# UsbToUart.net
KiCad netlist of a schematic drawn in Altium Designer
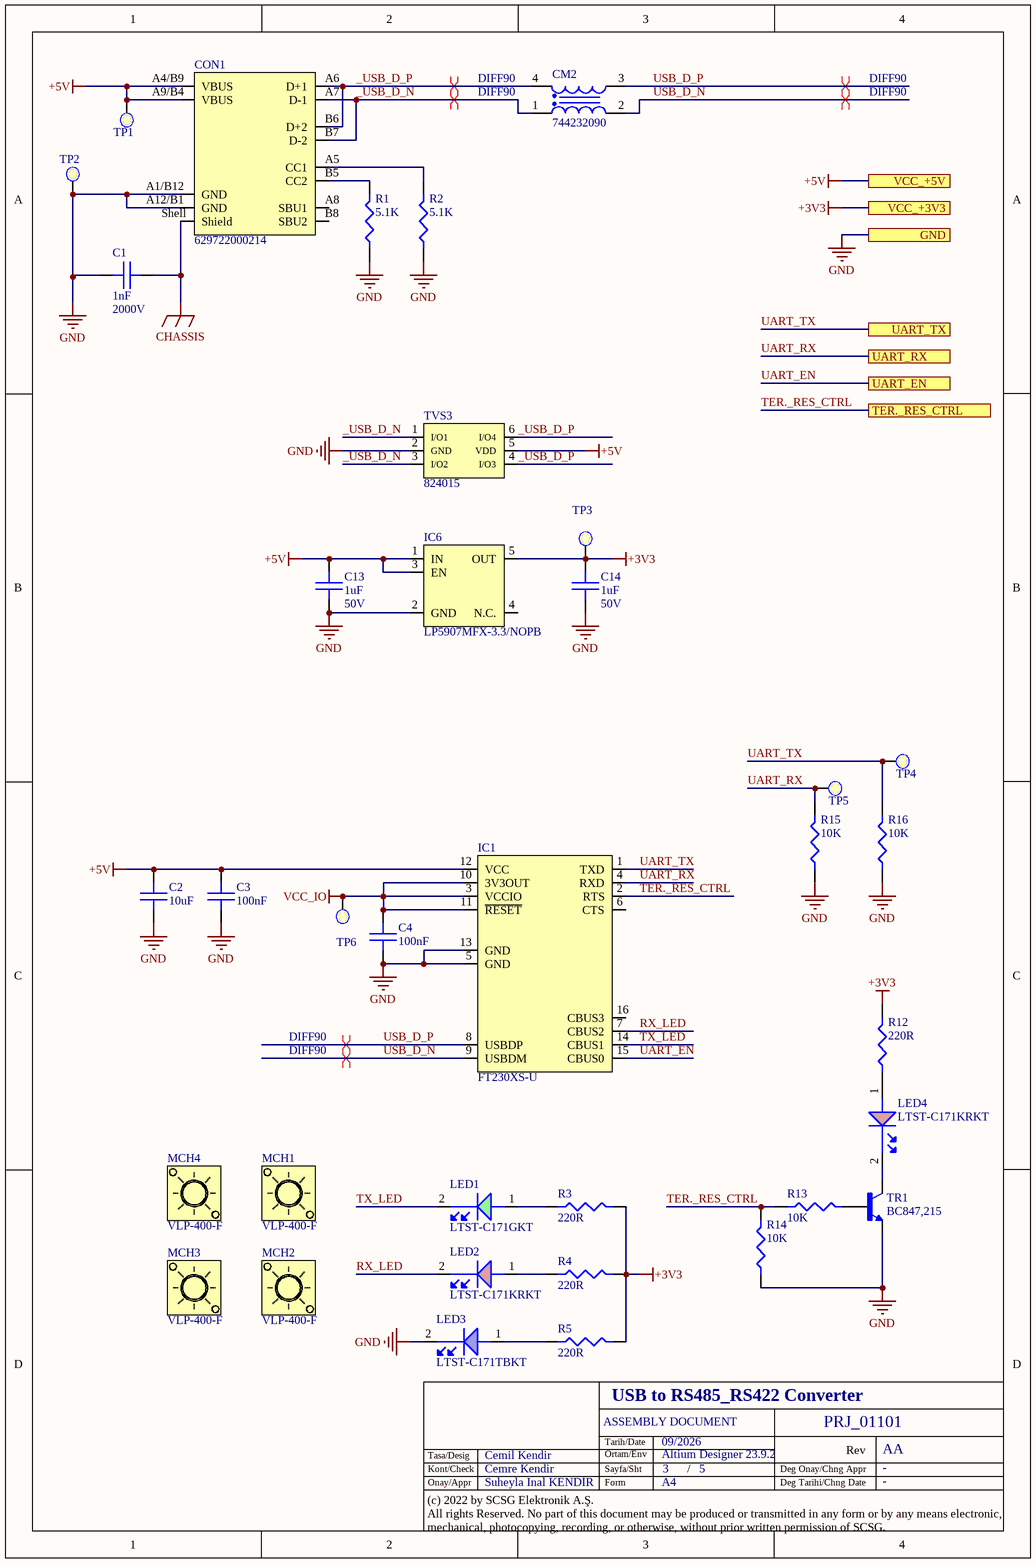
[diagram p0: UsbToUart.SchDoc]

(export (version "E")
  (design (tool "Eeschema 10.0.6"))
  (components
    (comp (ref "C1")
      (value "1nF")
      (footprint "C1206")
      (description "1nF, 2kV, X7R, 1206")
      (fields
        (field (name "MANUFACTURER") "Yageo")
        (field (name "MANUFACTURER PART NUMBER") "CS1206KKX7RDBB102")
        (field (name "VOLTAGE RATING") "2000V")
      )
      (libsource (lib "Capacitor") (part "CS1206KKX7RDBB102"))
    )
    (comp (ref "C2")
      (value "10uF")
      (footprint "C0805")
      (description "10uF ,10V ,X7R ,0805")
      (fields
        (field (name "MANUFACTURER") "Yageo")
        (field (name "MANUFACTURER PART NUMBER") "CC0805KFX7R6BB106")
      )
      (libsource (lib "Capacitor") (part "CC0805KFX7R6BB106"))
    )
    (comp (ref "C3")
      (value "100nF")
      (footprint "C0603")
      (description "100nF, 25V, X7R, 0603")
      (fields
        (field (name "MANUFACTURER") "Yageo")
        (field (name "MANUFACTURER PART NUMBER") "CC0603KRX7R8BB104")
      )
      (libsource (lib "Capacitor") (part "CC0603KRX7R8BB104"))
    )
    (comp (ref "C4")
      (value "100nF")
      (footprint "C0603")
      (description "100nF, 25V, X7R, 0603")
      (fields
        (field (name "MANUFACTURER") "Yageo")
        (field (name "MANUFACTURER PART NUMBER") "CC0603KRX7R8BB104")
      )
      (libsource (lib "Capacitor") (part "CC0603KRX7R8BB104"))
    )
    (comp (ref "C13")
      (value "1uF")
      (footprint "C0603")
      (description "1uF, 50V, X7R, 0603")
      (fields
        (field (name "MANUFACTURER") "Yageo")
        (field (name "MANUFACTURER PART NUMBER") "CC0603KRX7R9BB105")
        (field (name "VOLTAGE RATING") "50V")
      )
      (libsource (lib "Capacitor") (part "CC0603KRX7R9BB105"))
    )
    (comp (ref "C14")
      (value "1uF")
      (footprint "C0603")
      (description "1uF, 50V, X7R, 0603")
      (fields
        (field (name "MANUFACTURER") "Yageo")
        (field (name "MANUFACTURER PART NUMBER") "CC0603KRX7R9BB105")
        (field (name "VOLTAGE RATING") "50V")
      )
      (libsource (lib "Capacitor") (part "CC0603KRX7R9BB105"))
    )
    (comp (ref "CM2")
      (value "744232090")
      (footprint "WE-CNSW_1206")
      (description "Common Mode Chokes Dual 90Ohm 100MHz 370mA SMD T/R")
      (fields (field (name "MANUFACTURER") "Wurth Electronics"))
      (libsource (lib "Inductor") (part "744232090"))
    )
    (comp (ref "CON1")
      (value "629722000214")
      (footprint "629722000214")
      (description "Wr-com_usb 2.0_TYPE C_horizontal")
      (fields (field (name "MANUFACTURER") "Wurth Elektronik"))
      (libsource (lib "Connectors") (part "629722000214"))
    )
    (comp (ref "IC1")
      (value "FT230XS-U")
      (footprint "SSOP-16")
      (description "USB Interface IC USB to Basic Serial UART IC SSOP-16")
      (fields (field (name "MANUFACTURER") "FTDI"))
      (libsource (lib "IntegratedCircuit") (part "FT230XS-U"))
    )
    (comp (ref "IC6")
      (value "LP5907MFX-3.3/NOPB")
      (footprint "SOT23-5")
      (description "Linear Voltage Regulator IC Positive Fixed 1 Output 250mA SOT-23-5")
      (fields (field (name "MANUFACTURER") "TEXAS"))
      (libsource (lib "IntegratedCircuit") (part "LP5907MFX-3.3/NOPB"))
    )
    (comp (ref "LED1")
      (value "LTST-C171GKT")
      (footprint "0805_green")
      (description "LED GREEN CLEAR CHIP SMD")
      (fields (field (name "MANUFACTURER") "Vishay Lite-On"))
      (libsource (lib "Diode") (part "LTST-C171GKT"))
    )
    (comp (ref "LED2")
      (value "LTST-C171KRKT")
      (footprint "0805_RED")
      (description "LED RED CLEAR SMD")
      (fields (field (name "MANUFACTURER") "Vishay Lite-On"))
      (libsource (lib "Diode") (part "LTST-C171KRKT"))
    )
    (comp (ref "LED3")
      (value "LTST-C171TBKT")
      (footprint "0805_blue")
      (description "LED BLUE CLEAR CHIP SMD")
      (fields (field (name "MANUFACTURER") "Vishay Lite-On"))
      (libsource (lib "Diode") (part "LTST-C171TBKT"))
    )
    (comp (ref "LED4")
      (value "LTST-C171KRKT")
      (footprint "0805_RED")
      (description "LED RED CLEAR SMD")
      (fields (field (name "MANUFACTURER") "Vishay Lite-On"))
      (libsource (lib "Diode") (part "LTST-C171KRKT"))
    )
    (comp (ref "MCH1")
      (value "VLP-400-F")
      (footprint "VLP-400-F")
      (description "Bivar straight light guide, rigidity, PCBinstall, 4.1 x 4.1 x 10.2mm")
      (fields (field (name "MANUFACTURER") "Bivar"))
      (libsource (lib "Mechanical") (part "VLP-400-F"))
    )
    (comp (ref "MCH2")
      (value "VLP-400-F")
      (footprint "VLP-400-F")
      (description "Bivar straight light guide, rigidity, PCBinstall, 4.1 x 4.1 x 10.2mm")
      (fields (field (name "MANUFACTURER") "Bivar"))
      (libsource (lib "Mechanical") (part "VLP-400-F"))
    )
    (comp (ref "MCH3")
      (value "VLP-400-F")
      (footprint "VLP-400-F")
      (description "Bivar straight light guide, rigidity, PCBinstall, 4.1 x 4.1 x 10.2mm")
      (fields (field (name "MANUFACTURER") "Bivar"))
      (libsource (lib "Mechanical") (part "VLP-400-F"))
    )
    (comp (ref "MCH4")
      (value "VLP-400-F")
      (footprint "VLP-400-F")
      (description "Bivar straight light guide, rigidity, PCBinstall, 4.1 x 4.1 x 10.2mm")
      (fields (field (name "MANUFACTURER") "Bivar"))
      (libsource (lib "Mechanical") (part "VLP-400-F"))
    )
    (comp (ref "R1")
      (value "5.1K")
      (footprint "R0402")
      (description "5.1K, %1, 1/16W, 0402")
      (fields
        (field (name "MANUFACTURER") "YAGEO")
        (field (name "MANUFACTURER PART NUMBER") "RC0402FR-075K1L")
      )
      (libsource (lib "Resistor") (part "RC0402FR-075K1L"))
    )
    (comp (ref "R2")
      (value "5.1K")
      (footprint "R0402")
      (description "5.1K, %1, 1/16W, 0402")
      (fields
        (field (name "MANUFACTURER") "YAGEO")
        (field (name "MANUFACTURER PART NUMBER") "RC0402FR-075K1L")
      )
      (libsource (lib "Resistor") (part "RC0402FR-075K1L"))
    )
    (comp (ref "R3")
      (value "220R")
      (footprint "R0603")
      (description "220R, %1, 1/10W, 0603")
      (fields
        (field (name "MANUFACTURER") "YAGEO")
        (field (name "MANUFACTURER PART NUMBER") "RC0603FR-07220RL")
      )
      (libsource (lib "Resistor") (part "RC0603FR-07220RL"))
    )
    (comp (ref "R4")
      (value "220R")
      (footprint "R0603")
      (description "220R, %1, 1/10W, 0603")
      (fields
        (field (name "MANUFACTURER") "YAGEO")
        (field (name "MANUFACTURER PART NUMBER") "RC0603FR-07220RL")
      )
      (libsource (lib "Resistor") (part "RC0603FR-07220RL"))
    )
    (comp (ref "R5")
      (value "220R")
      (footprint "R0603")
      (description "220R, %1, 1/10W, 0603")
      (fields
        (field (name "MANUFACTURER") "YAGEO")
        (field (name "MANUFACTURER PART NUMBER") "RC0603FR-07220RL")
      )
      (libsource (lib "Resistor") (part "RC0603FR-07220RL"))
    )
    (comp (ref "R12")
      (value "220R")
      (footprint "R0603")
      (description "220R, %1, 1/10W, 0603")
      (fields
        (field (name "MANUFACTURER") "YAGEO")
        (field (name "MANUFACTURER PART NUMBER") "RC0603FR-07220RL")
      )
      (libsource (lib "Resistor") (part "RC0603FR-07220RL"))
    )
    (comp (ref "R13")
      (value "10K")
      (footprint "R0603")
      (description "10K, %1, 1/10W, 0603")
      (fields
        (field (name "MANUFACTURER") "YAGEO")
        (field (name "MANUFACTURER PART NUMBER") "RT0603FRE0710KL")
      )
      (libsource (lib "Resistor") (part "RT0603FRE0710KL"))
    )
    (comp (ref "R14")
      (value "10K")
      (footprint "R0603")
      (description "10K, %1, 1/10W, 0603")
      (fields
        (field (name "MANUFACTURER") "YAGEO")
        (field (name "MANUFACTURER PART NUMBER") "RT0603FRE0710KL")
      )
      (libsource (lib "Resistor") (part "RT0603FRE0710KL"))
    )
    (comp (ref "R15")
      (value "10K")
      (footprint "R0603")
      (description "10K, %1, 1/10W, 0603")
      (fields
        (field (name "MANUFACTURER") "YAGEO")
        (field (name "MANUFACTURER PART NUMBER") "RT0603FRE0710KL")
      )
      (libsource (lib "Resistor") (part "RT0603FRE0710KL"))
    )
    (comp (ref "R16")
      (value "10K")
      (footprint "R0603")
      (description "10K, %1, 1/10W, 0603")
      (fields
        (field (name "MANUFACTURER") "YAGEO")
        (field (name "MANUFACTURER PART NUMBER") "RT0603FRE0710KL")
      )
      (libsource (lib "Resistor") (part "RT0603FRE0710KL"))
    )
    (comp (ref "TP1")
      (value "TestPoint1")
      (footprint "SMD_1mmPoint")
      (description "test ölçüm noktası")
      (fields (field (name "MANUFACTURER") "NO BOM DEVICE"))
      (libsource (lib "Connectors") (part "TestPoint1"))
    )
    (comp (ref "TP2")
      (value "TestPoint1")
      (footprint "SMD_1mmPoint")
      (description "test ölçüm noktası")
      (fields (field (name "MANUFACTURER") "NO BOM DEVICE"))
      (libsource (lib "Connectors") (part "TestPoint1"))
    )
    (comp (ref "TP3")
      (value "TestPoint1")
      (footprint "SMD_1mmPoint")
      (description "test ölçüm noktası")
      (fields (field (name "MANUFACTURER") "NO BOM DEVICE"))
      (libsource (lib "Connectors") (part "TestPoint1"))
    )
    (comp (ref "TP4")
      (value "TestPoint1")
      (footprint "SMD_1mmPoint")
      (description "test ölçüm noktası")
      (fields (field (name "MANUFACTURER") "NO BOM DEVICE"))
      (libsource (lib "Connectors") (part "TestPoint1"))
    )
    (comp (ref "TP5")
      (value "TestPoint1")
      (footprint "SMD_1mmPoint")
      (description "test ölçüm noktası")
      (fields (field (name "MANUFACTURER") "NO BOM DEVICE"))
      (libsource (lib "Connectors") (part "TestPoint1"))
    )
    (comp (ref "TP6")
      (value "TestPoint1")
      (footprint "SMD_1mmPoint")
      (description "test ölçüm noktası")
      (fields (field (name "MANUFACTURER") "NO BOM DEVICE"))
      (libsource (lib "Connectors") (part "TestPoint1"))
    )
    (comp (ref "TR1")
      (value "BC847,215")
      (footprint "SOT23-3")
      (description "TRANS NPN 45V 0.1A SOT23")
      (fields (field (name "MANUFACTURER") "Nexperia"))
      (libsource (lib "Transistor") (part "BC847,215"))
    )
    (comp (ref "TVS3")
      (value "824015")
      (footprint "SOT-23-6")
      (description "WURTH ELEKTRONIK - 824015 - TVS Diode, 82401 Series, Bidirectional, 5 V, 13 V, SOT-23, 6 Pins")
      (fields (field (name "MANUFACTURER") "Wurth Electronics"))
      (libsource (lib "Diode") (part "824015"))
    )
  )
  (nets
    (net (code "1") (name "+3V3") (class "Default")
      (node (ref "C14") (pin "2") (pintype "passive"))
      (node (ref "IC6") (pin "5") (pinfunction "OUT_5") (pintype "passive"))
      (node (ref "R12") (pin "2") (pinfunction "2_2") (pintype "passive"))
      (node (ref "R3") (pin "2") (pinfunction "2_2") (pintype "passive"))
      (node (ref "R4") (pin "2") (pinfunction "2_2") (pintype "passive"))
      (node (ref "R5") (pin "2") (pinfunction "2_2") (pintype "passive"))
      (node (ref "TP3") (pin "1") (pinfunction "1_1") (pintype "passive"))
    )
    (net (code "2") (name "+5V") (class "Default")
      (node (ref "C13") (pin "2") (pintype "passive"))
      (node (ref "C2") (pin "2") (pintype "passive"))
      (node (ref "C3") (pin "2") (pintype "passive"))
      (node (ref "CON1") (pin "A4/B9") (pinfunction "VBUS_A4/B9") (pintype "passive"))
      (node (ref "CON1") (pin "A9/B4") (pinfunction "VBUS_A9/B4") (pintype "passive"))
      (node (ref "IC1") (pin "12") (pinfunction "VCC_12") (pintype "passive"))
      (node (ref "IC6") (pin "1") (pinfunction "IN_1") (pintype "passive"))
      (node (ref "IC6") (pin "3") (pinfunction "EN_3") (pintype "passive"))
      (node (ref "TP1") (pin "1") (pinfunction "1_1") (pintype "passive"))
      (node (ref "TVS3") (pin "5") (pinfunction "VDD_5") (pintype "passive"))
    )
    (net (code "3") (name "/RX_LED") (class "Default")
      (node (ref "IC1") (pin "7") (pinfunction "CBUS2_7") (pintype "passive"))
      (node (ref "LED2") (pin "2") (pinfunction "2_2") (pintype "passive"))
    )
    (net (code "4") (name "/TER._RES_CTRL") (class "Default")
      (node (ref "IC1") (pin "2") (pinfunction "RTS_2") (pintype "passive"))
      (node (ref "R13") (pin "1") (pinfunction "1_1") (pintype "passive"))
      (node (ref "R14") (pin "2") (pinfunction "2_2") (pintype "passive"))
    )
    (net (code "5") (name "/TX_LED") (class "Default")
      (node (ref "IC1") (pin "14") (pinfunction "CBUS1_14") (pintype "passive"))
      (node (ref "LED1") (pin "2") (pinfunction "2_2") (pintype "passive"))
    )
    (net (code "6") (name "/UART_EN") (class "Default")
      (node (ref "IC1") (pin "15") (pinfunction "CBUS0_15") (pintype "passive"))
    )
    (net (code "7") (name "/UART_RX") (class "Default")
      (node (ref "IC1") (pin "4") (pinfunction "RXD_4") (pintype "passive"))
      (node (ref "R15") (pin "2") (pinfunction "2_2") (pintype "passive"))
      (node (ref "TP5") (pin "1") (pinfunction "1_1") (pintype "passive"))
    )
    (net (code "8") (name "/UART_TX") (class "Default")
      (node (ref "IC1") (pin "1") (pinfunction "TXD_1") (pintype "passive"))
      (node (ref "R16") (pin "2") (pinfunction "2_2") (pintype "passive"))
      (node (ref "TP4") (pin "1") (pinfunction "1_1") (pintype "passive"))
    )
    (net (code "9") (name "/USB_D_N") (class "Default")
      (node (ref "CM2") (pin "2") (pinfunction "2_2") (pintype "passive"))
      (node (ref "IC1") (pin "9") (pinfunction "USBDM_9") (pintype "passive"))
    )
    (net (code "10") (name "/USB_D_P") (class "Default")
      (node (ref "CM2") (pin "3") (pinfunction "3_3") (pintype "passive"))
      (node (ref "IC1") (pin "8") (pinfunction "USBDP_8") (pintype "passive"))
    )
    (net (code "11") (name "/_USB_D_N") (class "Default")
      (node (ref "CM2") (pin "1") (pinfunction "1_1") (pintype "passive"))
      (node (ref "CON1") (pin "A7") (pinfunction "D-1_A7") (pintype "passive"))
      (node (ref "CON1") (pin "B7") (pinfunction "D-2_B7") (pintype "passive"))
      (node (ref "TVS3") (pin "1") (pinfunction "I/O1_1") (pintype "passive"))
      (node (ref "TVS3") (pin "3") (pinfunction "I/O2_3") (pintype "passive"))
    )
    (net (code "12") (name "/_USB_D_P") (class "Default")
      (node (ref "CM2") (pin "4") (pinfunction "4_4") (pintype "passive"))
      (node (ref "CON1") (pin "A6") (pinfunction "D+1_A6") (pintype "passive"))
      (node (ref "CON1") (pin "B6") (pinfunction "D+2_B6") (pintype "passive"))
      (node (ref "TVS3") (pin "4") (pinfunction "I/O3_4") (pintype "passive"))
      (node (ref "TVS3") (pin "6") (pinfunction "I/O4_6") (pintype "passive"))
    )
    (net (code "13") (name "CHASSIS") (class "Default")
      (node (ref "C1") (pin "2") (pintype "passive"))
      (node (ref "CON1") (pin "Shell") (pinfunction "Shield_Shell") (pintype "passive"))
    )
    (net (code "14") (name "GND") (class "Default")
      (node (ref "C1") (pin "1") (pintype "passive"))
      (node (ref "C13") (pin "1") (pintype "passive"))
      (node (ref "C14") (pin "1") (pintype "passive"))
      (node (ref "C2") (pin "1") (pintype "passive"))
      (node (ref "C3") (pin "1") (pintype "passive"))
      (node (ref "C4") (pin "1") (pintype "passive"))
      (node (ref "CON1") (pin "A1/B12") (pinfunction "GND_A1/B12") (pintype "passive"))
      (node (ref "CON1") (pin "A12/B1") (pinfunction "GND_A12/B1") (pintype "passive"))
      (node (ref "IC1") (pin "13") (pinfunction "GND_13") (pintype "passive"))
      (node (ref "IC1") (pin "5") (pinfunction "GND_5") (pintype "passive"))
      (node (ref "IC6") (pin "2") (pinfunction "GND_2") (pintype "passive"))
      (node (ref "LED3") (pin "2") (pinfunction "2_2") (pintype "passive"))
      (node (ref "R1") (pin "1") (pinfunction "1_1") (pintype "passive"))
      (node (ref "R14") (pin "1") (pinfunction "1_1") (pintype "passive"))
      (node (ref "R15") (pin "1") (pinfunction "1_1") (pintype "passive"))
      (node (ref "R16") (pin "1") (pinfunction "1_1") (pintype "passive"))
      (node (ref "R2") (pin "1") (pinfunction "1_1") (pintype "passive"))
      (node (ref "TP2") (pin "1") (pinfunction "1_1") (pintype "passive"))
      (node (ref "TR1") (pin "2") (pinfunction "E_2") (pintype "passive"))
      (node (ref "TVS3") (pin "2") (pinfunction "GND_2") (pintype "passive"))
    )
    (net (code "15") (name "Net-(CON1-CC1)") (class "Default")
      (node (ref "CON1") (pin "A5") (pinfunction "CC1_A5") (pintype "passive"))
      (node (ref "R2") (pin "2") (pinfunction "2_2") (pintype "passive"))
    )
    (net (code "16") (name "Net-(CON1-CC2)") (class "Default")
      (node (ref "CON1") (pin "B5") (pinfunction "CC2_B5") (pintype "passive"))
      (node (ref "R1") (pin "2") (pinfunction "2_2") (pintype "passive"))
    )
    (net (code "17") (name "Net-(LED1-Pad1)") (class "Default")
      (node (ref "LED1") (pin "1") (pinfunction "1_1") (pintype "passive"))
      (node (ref "R3") (pin "1") (pinfunction "1_1") (pintype "passive"))
    )
    (net (code "18") (name "Net-(LED2-Pad1)") (class "Default")
      (node (ref "LED2") (pin "1") (pinfunction "1_1") (pintype "passive"))
      (node (ref "R4") (pin "1") (pinfunction "1_1") (pintype "passive"))
    )
    (net (code "19") (name "Net-(LED3-Pad1)") (class "Default")
      (node (ref "LED3") (pin "1") (pinfunction "1_1") (pintype "passive"))
      (node (ref "R5") (pin "1") (pinfunction "1_1") (pintype "passive"))
    )
    (net (code "20") (name "Net-(LED4-Pad1)") (class "Default")
      (node (ref "LED4") (pin "1") (pinfunction "1_1") (pintype "passive"))
      (node (ref "R12") (pin "1") (pinfunction "1_1") (pintype "passive"))
    )
    (net (code "21") (name "Net-(TR1-B)") (class "Default")
      (node (ref "R13") (pin "2") (pinfunction "2_2") (pintype "passive"))
      (node (ref "TR1") (pin "1") (pinfunction "B_1") (pintype "passive"))
    )
    (net (code "22") (name "Net-(TR1-C)") (class "Default")
      (node (ref "LED4") (pin "2") (pinfunction "2_2") (pintype "passive"))
      (node (ref "TR1") (pin "3") (pinfunction "C_3") (pintype "passive"))
    )
    (net (code "23") (name "VCC_IO") (class "Default")
      (node (ref "C4") (pin "2") (pintype "passive"))
      (node (ref "IC1") (pin "10") (pinfunction "3V3OUT_10") (pintype "passive"))
      (node (ref "IC1") (pin "11") (pinfunction "~{RESET}_11") (pintype "passive"))
      (node (ref "IC1") (pin "3") (pinfunction "VCCIO_3") (pintype "passive"))
      (node (ref "TP6") (pin "1") (pinfunction "1_1") (pintype "passive"))
    )
    (net (code "24") (name "unconnected-(CON1-SBU1-PadA8)") (class "Default")
      (node (ref "CON1") (pin "A8") (pinfunction "SBU1_A8") (pintype "passive"))
    )
    (net (code "25") (name "unconnected-(CON1-SBU2-PadB8)") (class "Default")
      (node (ref "CON1") (pin "B8") (pinfunction "SBU2_B8") (pintype "passive"))
    )
    (net (code "26") (name "unconnected-(IC1-CBUS3-Pad16)") (class "Default")
      (node (ref "IC1") (pin "16") (pinfunction "CBUS3_16") (pintype "passive"))
    )
    (net (code "27") (name "unconnected-(IC1-CTS-Pad6)") (class "Default")
      (node (ref "IC1") (pin "6") (pinfunction "CTS_6") (pintype "passive"))
    )
    (net (code "28") (name "unconnected-(IC6-N.C.-Pad4)") (class "Default")
      (node (ref "IC6") (pin "4") (pinfunction "N.C._4") (pintype "passive"))
    )
  )
)
